# RELAY17.net
KiCad netlist of a schematic drawn in Altium Designer
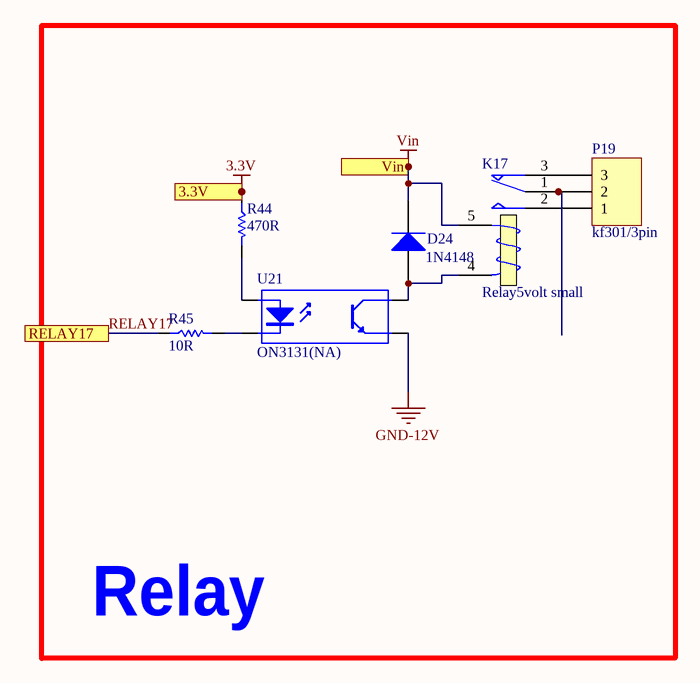
[diagram p0: RELAY17.SchDoc]

(export (version "E")
  (design (tool "Eeschema 10.0.6"))
  (components
    (comp (ref "D24")
      (value "1N4148")
      (footprint "sod123")
      (description "1 Amp General Purpose Rectifier")
      (fields (field (name "PUBLISHER") "Altium Limited"))
      (libsource (lib "Miscellaneous Devices") (part "Diode 1N4007"))
    )
    (comp (ref "K17")
      (value "Relay5volt small")
      (footprint "relay5_childern")
      (description "SPDT Relay")
      (fields (field (name "PUBLISHER") "Altium Limited"))
      (libsource (lib "FLIB") (part "Relay"))
    )
    (comp (ref "P19")
      (value "kf301/3pin")
      (footprint "Blue Connector 1*3 -kf301")
      (fields (field (name "PUBLISHER") "Altium Limited"))
      (libsource (lib "Miscellaneous Connectors") (part "Header 3"))
    )
    (comp (ref "R44")
      (value "470R")
      (footprint "0805/resistor")
      (description "Resistor")
      (fields (field (name "TOLERANCE") "5%") (field (name "POWER") "1/8 W"))
      (libsource (lib "skille") (part "Resistor"))
    )
    (comp (ref "R45")
      (value "10R")
      (footprint "0805/resistor")
      (description "Resistor")
      (fields (field (name "TOLERANCE") "5%") (field (name "POWER") "1/8 W"))
      (libsource (lib "skille") (part "Resistor"))
    )
    (comp (ref "U21")
      (value "ON3131(NA)")
      (footprint "OPTO_COUPLER")
      (description "4-Pin Phototransistor Optocoupler")
      (fields (field (name "PUBLISHER") "Altium Limited"))
      (libsource (lib "skille") (part "Optoisolator1"))
    )
  )
  (nets
    (net (code "1") (name "/RELAY17") (class "Default")
      (node (ref "R45") (pin "1") (pinfunction "1_1") (pintype "passive"))
    )
    (net (code "2") (name "3.3V") (class "Default")
      (node (ref "R44") (pin "1") (pinfunction "1_1") (pintype "passive"))
    )
    (net (code "3") (name "GND-12V") (class "Default")
      (node (ref "U21") (pin "3") (pinfunction "E_3") (pintype "passive"))
    )
    (net (code "4") (name "Net-(K17-COM)") (class "Default")
      (node (ref "K17") (pin "1") (pinfunction "COM_1") (pintype "passive"))
      (node (ref "P19") (pin "2") (pinfunction "2_2") (pintype "passive"))
    )
    (net (code "5") (name "Net-(K17-NO)") (class "Default")
      (node (ref "K17") (pin "2") (pinfunction "NO_2") (pintype "passive"))
      (node (ref "P19") (pin "1") (pinfunction "1_1") (pintype "passive"))
    )
    (net (code "6") (name "Net-(K17-T1)") (class "Default")
      (node (ref "K17") (pin "3") (pinfunction "T1_3") (pintype "passive"))
      (node (ref "P19") (pin "3") (pinfunction "3_3") (pintype "passive"))
    )
    (net (code "7") (name "Net-(K17-T2)") (class "Default")
      (node (ref "D24") (pin "A") (pinfunction "A_A") (pintype "passive"))
      (node (ref "K17") (pin "4") (pinfunction "T2_4") (pintype "passive"))
      (node (ref "U21") (pin "4") (pinfunction "C_4") (pintype "passive"))
    )
    (net (code "8") (name "Net-(U21-A)") (class "Default")
      (node (ref "R44") (pin "2") (pinfunction "2_2") (pintype "passive"))
      (node (ref "U21") (pin "1") (pinfunction "A_1") (pintype "passive"))
    )
    (net (code "9") (name "Net-(U21-K)") (class "Default")
      (node (ref "R45") (pin "2") (pinfunction "2_2") (pintype "passive"))
      (node (ref "U21") (pin "2") (pinfunction "K_2") (pintype "passive"))
    )
    (net (code "10") (name "Vin") (class "Default")
      (node (ref "D24") (pin "K") (pinfunction "K_K") (pintype "passive"))
      (node (ref "K17") (pin "5") (pinfunction "5_5") (pintype "passive"))
    )
  )
)
